# CRUVI.net
KiCad netlist of a schematic drawn in Altium Designer
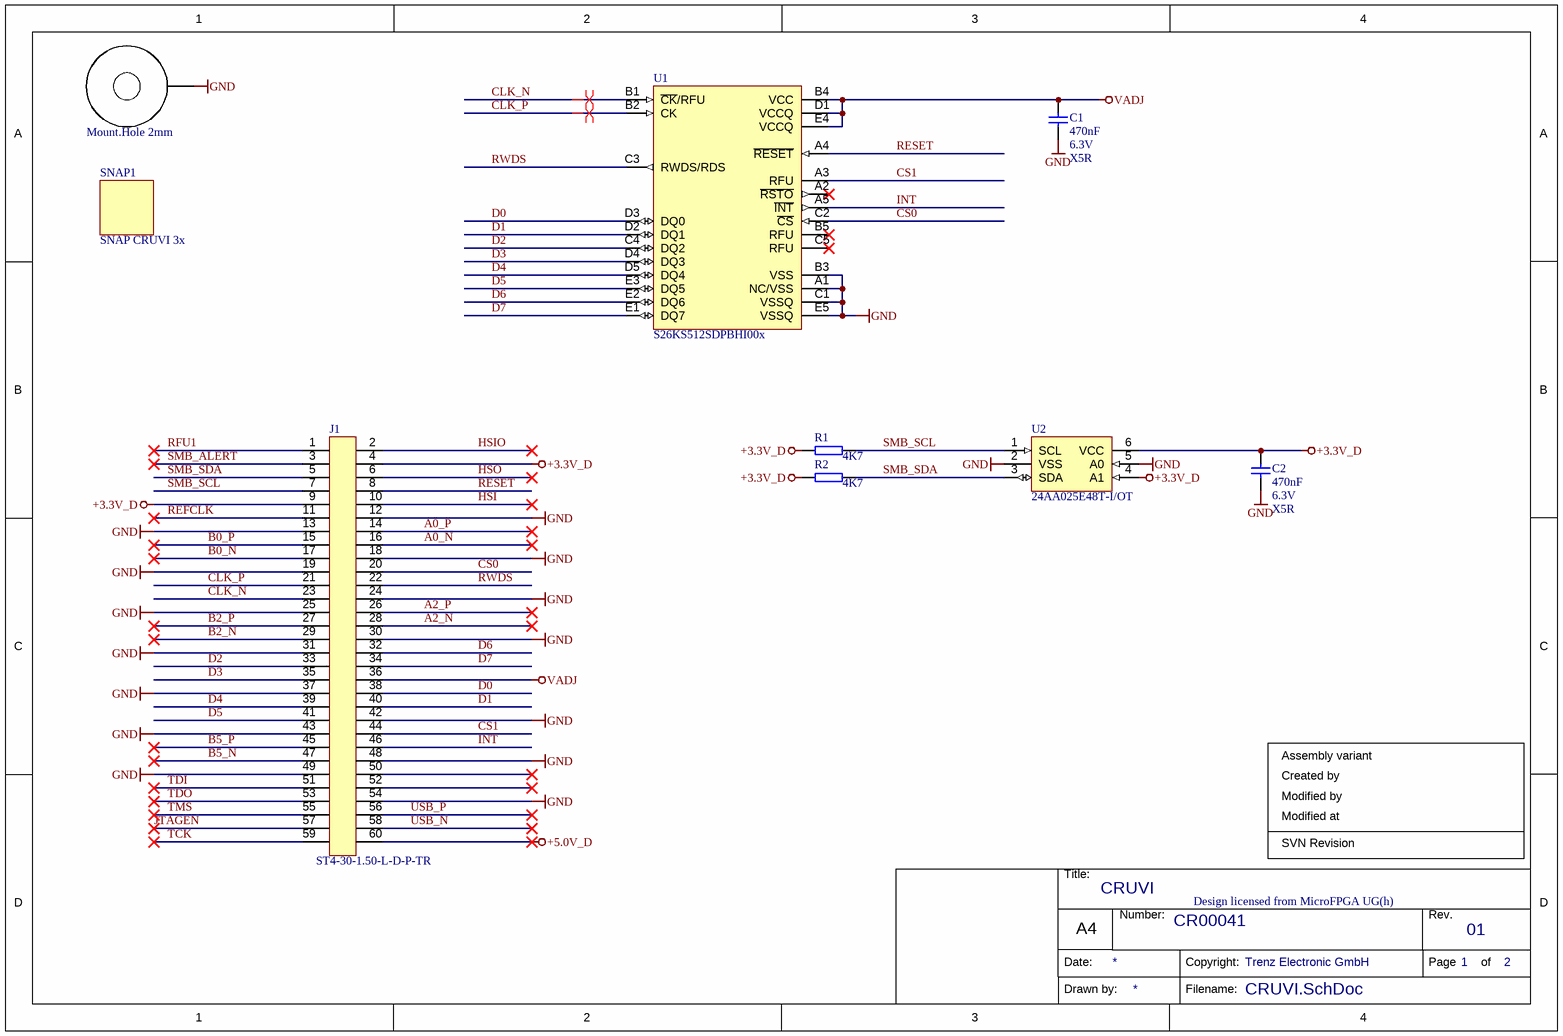
[diagram p0: CRUVI.SchDoc]

(export (version "E")
  (design (tool "Eeschema 10.0.6"))
  (components
    (comp (ref "C1")
      (value "470nF")
      (footprint "CAPC1005X55N")
      (description "KON 470nF 6,3V X5R SMD BF 1005 (0402)")
      (fields (field (name "VOLTAGE") "6.3V") (field (name "TECHNOLOGY") "X5R"))
      (libsource (lib "TE") (part "CAP-NP"))
    )
    (comp (ref "C2")
      (value "470nF")
      (footprint "CAPC1005X55N")
      (description "KON 470nF 6,3V X5R SMD BF 1005 (0402)")
      (fields (field (name "VOLTAGE") "6.3V") (field (name "TECHNOLOGY") "X5R"))
      (libsource (lib "TE") (part "CAP-NP"))
    )
    (comp (ref "H3") (value "Mount.Hole 2mm") (footprint "MHole2_2mm") (libsource (lib "TE") (part "MHole")))
    (comp (ref "J1")
      (value "ST4-30-1.50-L-D-P-TR")
      (footprint "ST4-30-1_50-L-D")
      (libsource (lib "TE") (part "CON-60"))
    )
    (comp (ref "R1")
      (value "4K7")
      (footprint "RESC1005X40N")
      (description "WID SMD 4K7 1% 0,063W BF 1005 (0402)")
      (fields (field (name "TOLERANCE") "1%"))
      (libsource (lib "TE") (part "RES"))
    )
    (comp (ref "R2")
      (value "4K7")
      (footprint "RESC1005X40N")
      (description "WID SMD 4K7 1% 0,063W BF 1005 (0402)")
      (fields (field (name "TOLERANCE") "1%"))
      (libsource (lib "TE") (part "RES"))
    )
    (comp (ref "SNAP1")
      (value "SNAP CRUVI 3x")
      (footprint "CRUVI_3x_Snap")
      (description "SNAP for CRUVI 3x")
      (libsource (lib "TE") (part "DUMMY"))
    )
    (comp (ref "U1")
      (value "S26KS512SDPBHI00x")
      (footprint "BGA25C100P5X5_800X600X120N")
      (description "S26KS512SDPBHI00x 1.8V")
      (libsource (lib "TE") (part "S26KS512S"))
    )
    (comp (ref "U2")
      (value "24AA025E48T-I/OT")
      (footprint "SOT95P280X145-6N")
      (libsource (lib "TE") (part "24AA025E48"))
    )
  )
  (nets
    (net (code "1") (name "+3.3V_D") (class "Default")
      (node (ref "C2") (pin "1") (pinfunction "1_1") (pintype "passive"))
      (node (ref "J1") (pin "4") (pinfunction "4_4") (pintype "passive"))
      (node (ref "J1") (pin "9") (pinfunction "9_9") (pintype "passive"))
      (node (ref "R1") (pin "1") (pinfunction "1_1") (pintype "passive"))
      (node (ref "R2") (pin "1") (pinfunction "1_1") (pintype "passive"))
      (node (ref "U2") (pin "4") (pinfunction "A1_4") (pintype "input"))
      (node (ref "U2") (pin "6") (pinfunction "VCC_6") (pintype "power_in"))
    )
    (net (code "2") (name "+5.0V_D") (class "Default")
      (node (ref "J1") (pin "60") (pinfunction "60_60") (pintype "passive"))
    )
    (net (code "3") (name "/A0_N") (class "Default")
      (node (ref "J1") (pin "16") (pinfunction "16_16") (pintype "passive+no_connect"))
    )
    (net (code "4") (name "/A0_P") (class "Default")
      (node (ref "J1") (pin "14") (pinfunction "14_14") (pintype "passive+no_connect"))
    )
    (net (code "5") (name "/A2_N") (class "Default")
      (node (ref "J1") (pin "28") (pinfunction "28_28") (pintype "passive+no_connect"))
    )
    (net (code "6") (name "/A2_P") (class "Default")
      (node (ref "J1") (pin "26") (pinfunction "26_26") (pintype "passive+no_connect"))
    )
    (net (code "7") (name "/B0_N") (class "Default")
      (node (ref "J1") (pin "17") (pinfunction "17_17") (pintype "passive+no_connect"))
    )
    (net (code "8") (name "/B0_P") (class "Default")
      (node (ref "J1") (pin "15") (pinfunction "15_15") (pintype "passive+no_connect"))
    )
    (net (code "9") (name "/B2_N") (class "Default")
      (node (ref "J1") (pin "29") (pinfunction "29_29") (pintype "passive+no_connect"))
    )
    (net (code "10") (name "/B2_P") (class "Default")
      (node (ref "J1") (pin "27") (pinfunction "27_27") (pintype "passive+no_connect"))
    )
    (net (code "11") (name "/B5_N") (class "Default")
      (node (ref "J1") (pin "47") (pinfunction "47_47") (pintype "passive+no_connect"))
    )
    (net (code "12") (name "/B5_P") (class "Default")
      (node (ref "J1") (pin "45") (pinfunction "45_45") (pintype "passive+no_connect"))
    )
    (net (code "13") (name "/CLK_N") (class "Default")
      (node (ref "J1") (pin "23") (pinfunction "23_23") (pintype "passive"))
      (node (ref "U1") (pin "B1") (pinfunction "~{CK}/RFU_B1") (pintype "input"))
    )
    (net (code "14") (name "/CLK_P") (class "Default")
      (node (ref "J1") (pin "21") (pinfunction "21_21") (pintype "passive"))
      (node (ref "U1") (pin "B2") (pinfunction "CK_B2") (pintype "input"))
    )
    (net (code "15") (name "/CS0") (class "Default")
      (node (ref "J1") (pin "20") (pinfunction "20_20") (pintype "passive"))
      (node (ref "U1") (pin "C2") (pinfunction "~{CS}_C2") (pintype "input"))
    )
    (net (code "16") (name "/CS1") (class "Default")
      (node (ref "J1") (pin "44") (pinfunction "44_44") (pintype "passive"))
      (node (ref "U1") (pin "A3") (pinfunction "RFU_A3") (pintype "passive"))
    )
    (net (code "17") (name "/D0") (class "Default")
      (node (ref "J1") (pin "38") (pinfunction "38_38") (pintype "passive"))
      (node (ref "U1") (pin "D3") (pinfunction "DQ0_D3") (pintype "bidirectional"))
    )
    (net (code "18") (name "/D1") (class "Default")
      (node (ref "J1") (pin "40") (pinfunction "40_40") (pintype "passive"))
      (node (ref "U1") (pin "D2") (pinfunction "DQ1_D2") (pintype "bidirectional"))
    )
    (net (code "19") (name "/D2") (class "Default")
      (node (ref "J1") (pin "33") (pinfunction "33_33") (pintype "passive"))
      (node (ref "U1") (pin "C4") (pinfunction "DQ2_C4") (pintype "bidirectional"))
    )
    (net (code "20") (name "/D3") (class "Default")
      (node (ref "J1") (pin "35") (pinfunction "35_35") (pintype "passive"))
      (node (ref "U1") (pin "D4") (pinfunction "DQ3_D4") (pintype "bidirectional"))
    )
    (net (code "21") (name "/D4") (class "Default")
      (node (ref "J1") (pin "39") (pinfunction "39_39") (pintype "passive"))
      (node (ref "U1") (pin "D5") (pinfunction "DQ4_D5") (pintype "bidirectional"))
    )
    (net (code "22") (name "/D5") (class "Default")
      (node (ref "J1") (pin "41") (pinfunction "41_41") (pintype "passive"))
      (node (ref "U1") (pin "E3") (pinfunction "DQ5_E3") (pintype "bidirectional"))
    )
    (net (code "23") (name "/D6") (class "Default")
      (node (ref "J1") (pin "32") (pinfunction "32_32") (pintype "passive"))
      (node (ref "U1") (pin "E2") (pinfunction "DQ6_E2") (pintype "bidirectional"))
    )
    (net (code "24") (name "/D7") (class "Default")
      (node (ref "J1") (pin "34") (pinfunction "34_34") (pintype "passive"))
      (node (ref "U1") (pin "E1") (pinfunction "DQ7_E1") (pintype "bidirectional"))
    )
    (net (code "25") (name "/HSI") (class "Default")
      (node (ref "J1") (pin "10") (pinfunction "10_10") (pintype "passive+no_connect"))
    )
    (net (code "26") (name "/HSIO") (class "Default")
      (node (ref "J1") (pin "2") (pinfunction "2_2") (pintype "passive+no_connect"))
    )
    (net (code "27") (name "/HSO") (class "Default")
      (node (ref "J1") (pin "6") (pinfunction "6_6") (pintype "passive+no_connect"))
    )
    (net (code "28") (name "/INT") (class "Default")
      (node (ref "J1") (pin "46") (pinfunction "46_46") (pintype "passive"))
      (node (ref "U1") (pin "A5") (pinfunction "~{INT}_A5") (pintype "output"))
    )
    (net (code "29") (name "/JTAGEN") (class "Default")
      (node (ref "J1") (pin "57") (pinfunction "57_57") (pintype "passive+no_connect"))
    )
    (net (code "30") (name "/REFCLK") (class "Default")
      (node (ref "J1") (pin "11") (pinfunction "11_11") (pintype "passive+no_connect"))
    )
    (net (code "31") (name "/RESET") (class "Default")
      (node (ref "J1") (pin "8") (pinfunction "8_8") (pintype "passive"))
      (node (ref "U1") (pin "A4") (pinfunction "~{RESET}_A4") (pintype "input"))
    )
    (net (code "32") (name "/RFU1") (class "Default")
      (node (ref "J1") (pin "1") (pinfunction "1_1") (pintype "passive+no_connect"))
    )
    (net (code "33") (name "/RWDS") (class "Default")
      (node (ref "J1") (pin "22") (pinfunction "22_22") (pintype "passive"))
      (node (ref "U1") (pin "C3") (pinfunction "RWDS/RDS_C3") (pintype "output"))
    )
    (net (code "34") (name "/SMB_ALERT") (class "Default")
      (node (ref "J1") (pin "3") (pinfunction "3_3") (pintype "passive+no_connect"))
    )
    (net (code "35") (name "/SMB_SCL") (class "Default")
      (node (ref "J1") (pin "7") (pinfunction "7_7") (pintype "passive"))
      (node (ref "R1") (pin "2") (pinfunction "2_2") (pintype "passive"))
      (node (ref "U2") (pin "1") (pinfunction "SCL_1") (pintype "input"))
    )
    (net (code "36") (name "/SMB_SDA") (class "Default")
      (node (ref "J1") (pin "5") (pinfunction "5_5") (pintype "passive"))
      (node (ref "R2") (pin "2") (pinfunction "2_2") (pintype "passive"))
      (node (ref "U2") (pin "3") (pinfunction "SDA_3") (pintype "bidirectional"))
    )
    (net (code "37") (name "/TCK") (class "Default")
      (node (ref "J1") (pin "59") (pinfunction "59_59") (pintype "passive+no_connect"))
    )
    (net (code "38") (name "/TDI") (class "Default")
      (node (ref "J1") (pin "51") (pinfunction "51_51") (pintype "passive+no_connect"))
    )
    (net (code "39") (name "/TDO") (class "Default")
      (node (ref "J1") (pin "53") (pinfunction "53_53") (pintype "passive+no_connect"))
    )
    (net (code "40") (name "/TMS") (class "Default")
      (node (ref "J1") (pin "55") (pinfunction "55_55") (pintype "passive+no_connect"))
    )
    (net (code "41") (name "/USB_N") (class "Default")
      (node (ref "J1") (pin "58") (pinfunction "58_58") (pintype "passive+no_connect"))
    )
    (net (code "42") (name "/USB_P") (class "Default")
      (node (ref "J1") (pin "56") (pinfunction "56_56") (pintype "passive+no_connect"))
    )
    (net (code "43") (name "GND") (class "Default")
      (node (ref "C1") (pin "2") (pinfunction "2_2") (pintype "passive"))
      (node (ref "C2") (pin "2") (pinfunction "2_2") (pintype "passive"))
      (node (ref "H3") (pin "1") (pinfunction "1_1") (pintype "passive"))
      (node (ref "J1") (pin "12") (pinfunction "12_12") (pintype "passive"))
      (node (ref "J1") (pin "13") (pinfunction "13_13") (pintype "passive"))
      (node (ref "J1") (pin "18") (pinfunction "18_18") (pintype "passive"))
      (node (ref "J1") (pin "19") (pinfunction "19_19") (pintype "passive"))
      (node (ref "J1") (pin "24") (pinfunction "24_24") (pintype "passive"))
      (node (ref "J1") (pin "25") (pinfunction "25_25") (pintype "passive"))
      (node (ref "J1") (pin "30") (pinfunction "30_30") (pintype "passive"))
      (node (ref "J1") (pin "31") (pinfunction "31_31") (pintype "passive"))
      (node (ref "J1") (pin "37") (pinfunction "37_37") (pintype "passive"))
      (node (ref "J1") (pin "42") (pinfunction "42_42") (pintype "passive"))
      (node (ref "J1") (pin "43") (pinfunction "43_43") (pintype "passive"))
      (node (ref "J1") (pin "48") (pinfunction "48_48") (pintype "passive"))
      (node (ref "J1") (pin "49") (pinfunction "49_49") (pintype "passive"))
      (node (ref "J1") (pin "54") (pinfunction "54_54") (pintype "passive"))
      (node (ref "U1") (pin "A1") (pinfunction "NC/VSS_A1") (pintype "power_in"))
      (node (ref "U1") (pin "B3") (pinfunction "VSS_B3") (pintype "power_in"))
      (node (ref "U1") (pin "C1") (pinfunction "VSSQ_C1") (pintype "power_in"))
      (node (ref "U1") (pin "E5") (pinfunction "VSSQ_E5") (pintype "power_in"))
      (node (ref "U2") (pin "2") (pinfunction "VSS_2") (pintype "power_in"))
      (node (ref "U2") (pin "5") (pinfunction "A0_5") (pintype "input"))
    )
    (net (code "44") (name "VADJ") (class "Default")
      (node (ref "C1") (pin "1") (pinfunction "1_1") (pintype "passive"))
      (node (ref "J1") (pin "36") (pinfunction "36_36") (pintype "passive"))
      (node (ref "U1") (pin "B4") (pinfunction "VCC_B4") (pintype "power_in"))
      (node (ref "U1") (pin "D1") (pinfunction "VCCQ_D1") (pintype "power_in"))
      (node (ref "U1") (pin "E4") (pinfunction "VCCQ_E4") (pintype "power_in"))
    )
    (net (code "45") (name "unconnected-(J1-Pad50)") (class "Default")
      (node (ref "J1") (pin "50") (pinfunction "50_50") (pintype "passive+no_connect"))
    )
    (net (code "46") (name "unconnected-(J1-Pad52)") (class "Default")
      (node (ref "J1") (pin "52") (pinfunction "52_52") (pintype "passive+no_connect"))
    )
    (net (code "47") (name "unconnected-(U1-RFU-PadB5)") (class "Default")
      (node (ref "U1") (pin "B5") (pinfunction "RFU_B5") (pintype "passive+no_connect"))
    )
    (net (code "48") (name "unconnected-(U1-RFU-PadC5)") (class "Default")
      (node (ref "U1") (pin "C5") (pinfunction "RFU_C5") (pintype "passive+no_connect"))
    )
    (net (code "49") (name "unconnected-(U1-~{RSTO}-PadA2)") (class "Default")
      (node (ref "U1") (pin "A2") (pinfunction "~{RSTO}_A2") (pintype "output+no_connect"))
    )
  )
)
